# UVglasses.net
KiCad netlist of a schematic drawn in EAGLE
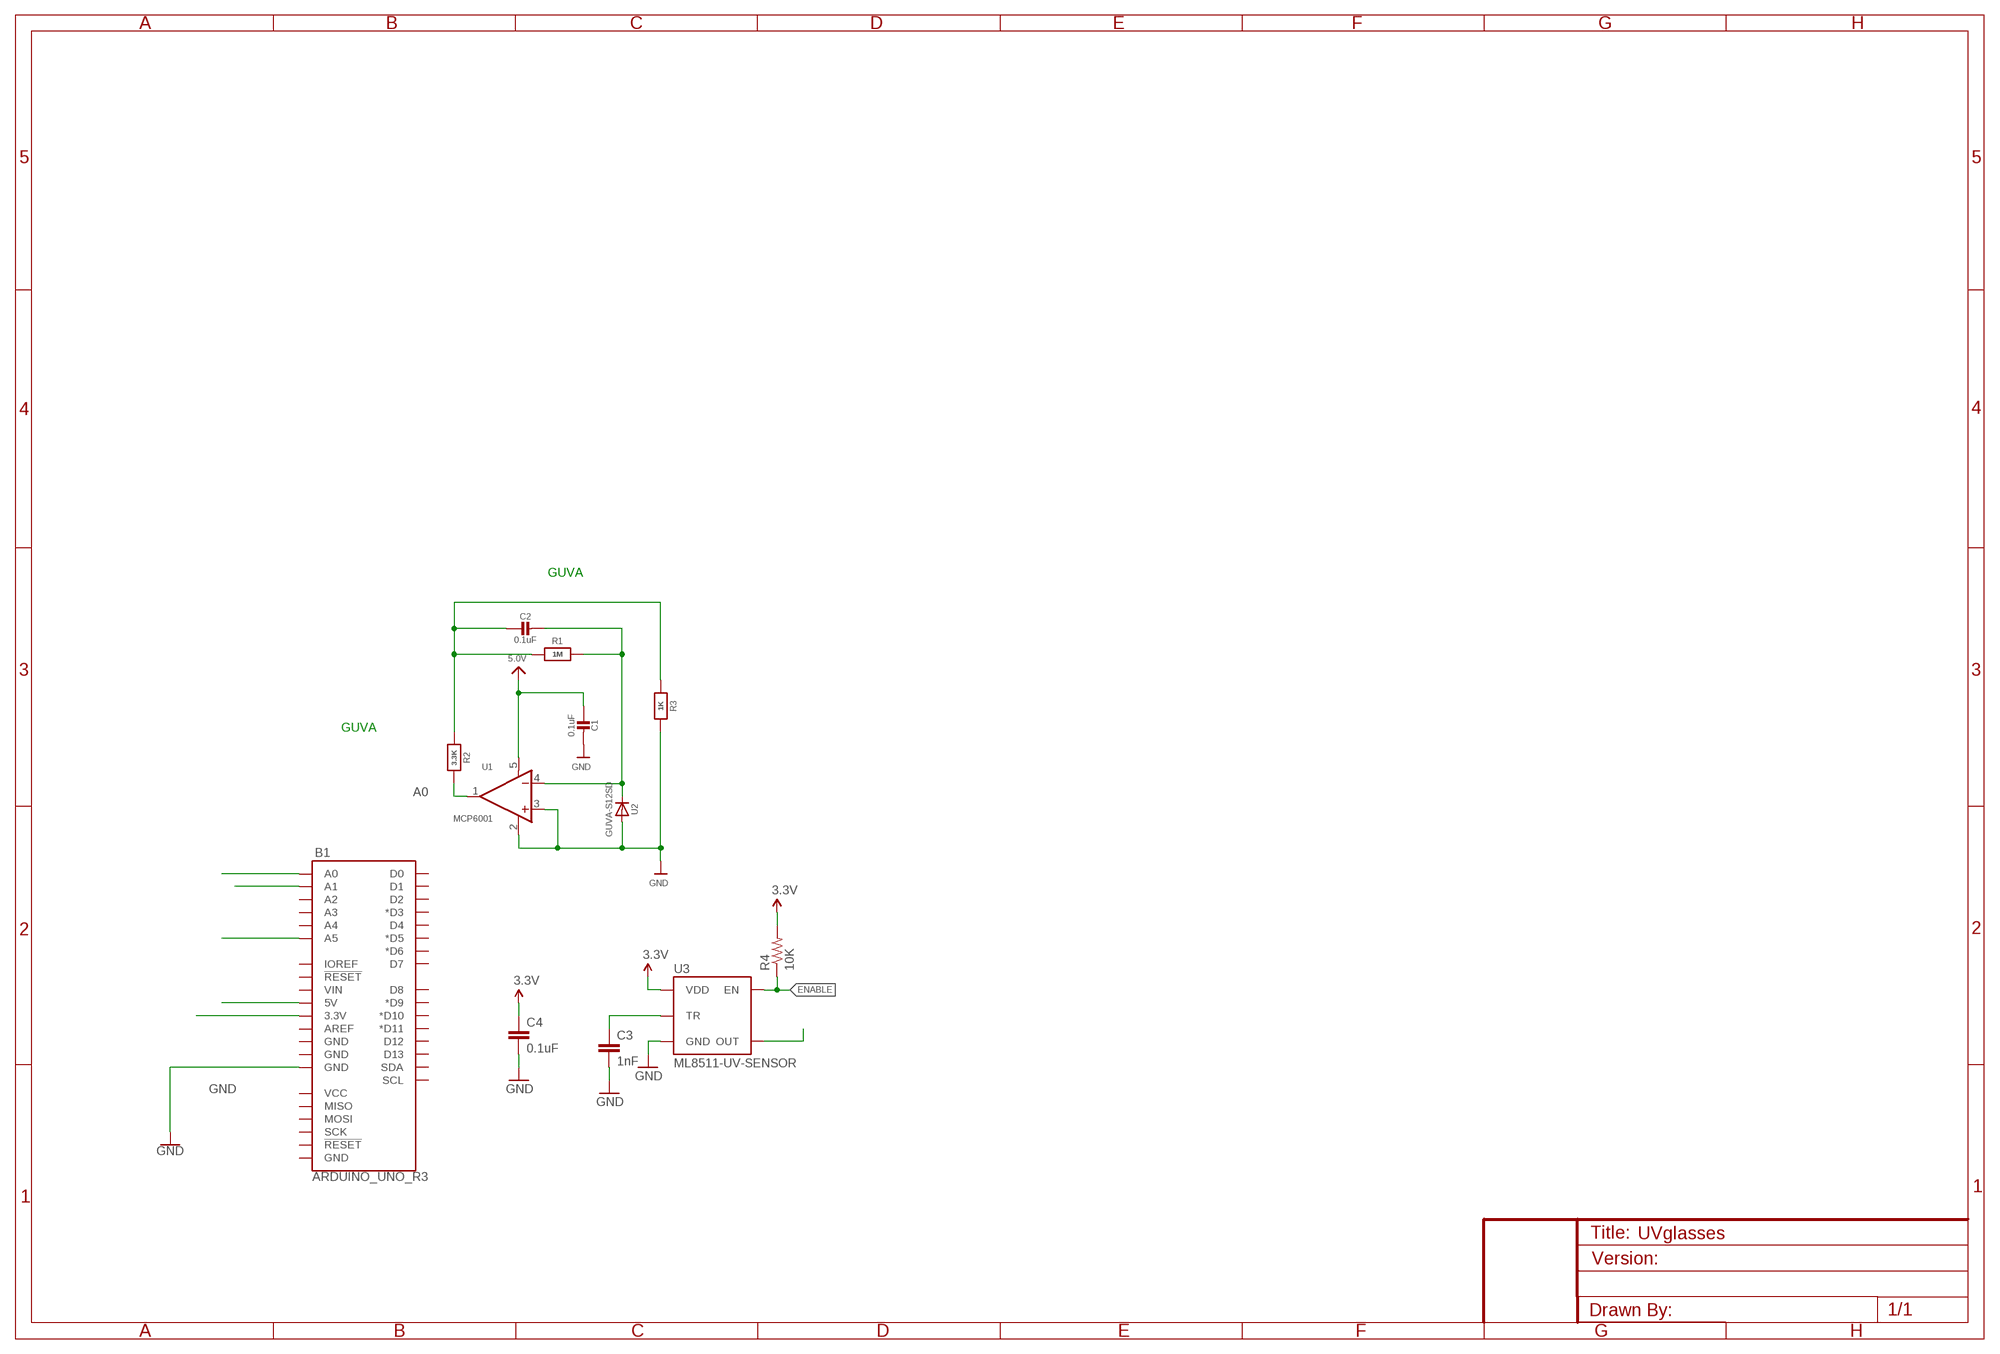
[diagram p0: schematic, sheet 1]

(export (version "E")
  (design (tool "Eeschema 10.0.6"))
  (components
    (comp (ref "B1")
      (value "ARDUINO_UNO_R3")
      (footprint "eagle-import:ARDUINO_R3")
      (libsource (lib "eagle-import") (part "ARDUINO_UNO_R3"))
    )
    (comp (ref "C1")
      (value "0.1uF")
      (footprint "eagle-import:0805-NO")
      (libsource (lib "eagle-import") (part "CAP_CERAMIC0805-NOOUTLINE"))
    )
    (comp (ref "C2")
      (value "0.1uF")
      (footprint "eagle-import:0805-NO")
      (libsource (lib "eagle-import") (part "CAP_CERAMIC0805-NOOUTLINE"))
    )
    (comp (ref "C3")
      (value "1nF")
      (footprint "eagle-import:0603-CAP")
      (libsource (lib "eagle-import") (part "1NF/1000PF-50V-10%(0603)"))
    )
    (comp (ref "C4")
      (value "0.1uF")
      (footprint "eagle-import:0603-CAP")
      (libsource (lib "eagle-import") (part "0.1UF-25V(+80/-20%)(0603)"))
    )
    (comp (ref "R1")
      (value "1M")
      (footprint "eagle-import:0805-NO")
      (libsource (lib "eagle-import") (part "RESISTOR0805_NOOUTLINE"))
    )
    (comp (ref "R2")
      (value "3.3K")
      (footprint "eagle-import:0805-NO")
      (libsource (lib "eagle-import") (part "RESISTOR0805_NOOUTLINE"))
    )
    (comp (ref "R3")
      (value "1K")
      (footprint "eagle-import:0805-NO")
      (libsource (lib "eagle-import") (part "RESISTOR0805_NOOUTLINE"))
    )
    (comp (ref "R4")
      (value "10K")
      (footprint "eagle-import:0603-RES")
      (libsource (lib "eagle-import") (part "10KOHM1/10W1%(0603)0603"))
    )
    (comp (ref "U1")
      (value "MCP6001")
      (footprint "eagle-import:SOT23-5")
      (libsource (lib "eagle-import") (part "OPAMP_SINGLESOT235"))
    )
    (comp (ref "U2")
      (value "GUVA-S12SD")
      (footprint "eagle-import:GUVA-S12SD")
      (libsource (lib "eagle-import") (part "UV_GUVA-S12SD"))
    )
    (comp (ref "U3")
      (value "ML8511-UV-SENSOR")
      (footprint "eagle-import:ML8511")
      (libsource (lib "eagle-import") (part "ML8511-UV-SENSORSMD"))
    )
  )
  (nets
    (net (code "1") (name "/A0") (class "Default")
      (node (ref "B1") (pin "A0") (pinfunction "A0_A0") (pintype "bidirectional"))
      (node (ref "R2") (pin "1") (pinfunction "1_1") (pintype "passive"))
      (node (ref "U1") (pin "1") (pinfunction "OUT_1") (pintype "output"))
    )
    (net (code "2") (name "/A1") (class "Default")
      (node (ref "B1") (pin "A1") (pinfunction "A1_A1") (pintype "bidirectional"))
      (node (ref "U3") (pin "8") (pinfunction "OUT_8") (pintype "output"))
    )
    (net (code "3") (name "3.3V") (class "Default")
      (node (ref "B1") (pin "3.3V") (pinfunction "3.3V_3.3V") (pintype "bidirectional"))
      (node (ref "B1") (pin "A5") (pinfunction "A5_A5") (pintype "bidirectional"))
      (node (ref "C4") (pin "1") (pinfunction "1_1") (pintype "passive"))
      (node (ref "R4") (pin "2") (pinfunction "2_2") (pintype "passive"))
      (node (ref "U3") (pin "7") (pinfunction "VDD_7") (pintype "power_in"))
    )
    (net (code "4") (name "5.0V") (class "Default")
      (node (ref "B1") (pin "5V") (pinfunction "5V_5V") (pintype "bidirectional"))
      (node (ref "C1") (pin "1") (pinfunction "1_1") (pintype "passive"))
      (node (ref "U1") (pin "5") (pinfunction "V+_5") (pintype "power_in"))
    )
    (net (code "5") (name "ENABLE") (class "Default")
      (node (ref "R4") (pin "1") (pinfunction "1_1") (pintype "passive"))
      (node (ref "U3") (pin "4") (pinfunction "EN_4") (pintype "input"))
    )
    (net (code "6") (name "GND") (class "Default")
      (node (ref "B1") (pin "GND@2") (pinfunction "GND_GND@2") (pintype "bidirectional"))
      (node (ref "C1") (pin "2") (pinfunction "2_2") (pintype "passive"))
      (node (ref "C3") (pin "2") (pinfunction "2_2") (pintype "passive"))
      (node (ref "C4") (pin "2") (pinfunction "2_2") (pintype "passive"))
      (node (ref "R3") (pin "1") (pinfunction "1_1") (pintype "passive"))
      (node (ref "U1") (pin "2") (pinfunction "V-_2") (pintype "power_in"))
      (node (ref "U1") (pin "3") (pinfunction "+IN_3") (pintype "input"))
      (node (ref "U2") (pin "A") (pinfunction "A_A") (pintype "passive"))
      (node (ref "U3") (pin "5") (pinfunction "GND_5") (pintype "power_in"))
    )
    (net (code "7") (name "Net-(C2-Pad1)") (class "Default")
      (node (ref "C2") (pin "1") (pinfunction "1_1") (pintype "passive"))
      (node (ref "R1") (pin "2") (pinfunction "2_2") (pintype "passive"))
      (node (ref "R2") (pin "2") (pinfunction "2_2") (pintype "passive"))
      (node (ref "R3") (pin "2") (pinfunction "2_2") (pintype "passive"))
    )
    (net (code "8") (name "Net-(U1--IN)") (class "Default")
      (node (ref "C2") (pin "2") (pinfunction "2_2") (pintype "passive"))
      (node (ref "R1") (pin "1") (pinfunction "1_1") (pintype "passive"))
      (node (ref "U1") (pin "4") (pinfunction "-IN_4") (pintype "input"))
      (node (ref "U2") (pin "K") (pinfunction "C_K") (pintype "passive"))
    )
    (net (code "9") (name "Net-(U3-TR)") (class "Default")
      (node (ref "C3") (pin "1") (pinfunction "1_1") (pintype "passive"))
      (node (ref "U3") (pin "10") (pinfunction "TR_10") (pintype "power_in"))
    )
    (net (code "10") (name "unconnected-(B1-*D3-PadD3)") (class "Default")
      (node (ref "B1") (pin "D3") (pinfunction "*D3_D3") (pintype "bidirectional"))
    )
    (net (code "11") (name "unconnected-(B1-*D5-PadD5)") (class "Default")
      (node (ref "B1") (pin "D5") (pinfunction "*D5_D5") (pintype "bidirectional"))
    )
    (net (code "12") (name "unconnected-(B1-*D6-PadD6)") (class "Default")
      (node (ref "B1") (pin "D6") (pinfunction "*D6_D6") (pintype "bidirectional"))
    )
    (net (code "13") (name "unconnected-(B1-*D9-PadD9)") (class "Default")
      (node (ref "B1") (pin "D9") (pinfunction "*D9_D9") (pintype "bidirectional"))
    )
    (net (code "14") (name "unconnected-(B1-*D10-PadD10)") (class "Default")
      (node (ref "B1") (pin "D10") (pinfunction "*D10_D10") (pintype "bidirectional"))
    )
    (net (code "15") (name "unconnected-(B1-*D11-PadD11)") (class "Default")
      (node (ref "B1") (pin "D11") (pinfunction "*D11_D11") (pintype "bidirectional"))
    )
    (net (code "16") (name "unconnected-(B1-GND-PadGND@1)") (class "Default")
      (node (ref "B1") (pin "GND@1") (pinfunction "GND_GND@1") (pintype "bidirectional"))
    )
    (net (code "17") (name "unconnected-(B1-GND-PadGND@3)") (class "Default")
      (node (ref "B1") (pin "GND@3") (pinfunction "GND_GND@3") (pintype "bidirectional"))
    )
    (net (code "18") (name "unconnected-(B1-GND-PadGND@4)") (class "Default")
      (node (ref "B1") (pin "GND@4") (pinfunction "GND_GND@4") (pintype "bidirectional"))
    )
    (net (code "19") (name "unconnected-(B1-PadA2)") (class "Default")
      (node (ref "B1") (pin "A2") (pinfunction "A2_A2") (pintype "bidirectional"))
    )
    (net (code "20") (name "unconnected-(B1-PadA3)") (class "Default")
      (node (ref "B1") (pin "A3") (pinfunction "A3_A3") (pintype "bidirectional"))
    )
    (net (code "21") (name "unconnected-(B1-PadA4)") (class "Default")
      (node (ref "B1") (pin "A4") (pinfunction "A4_A4") (pintype "bidirectional"))
    )
    (net (code "22") (name "unconnected-(B1-PadAREF)") (class "Default")
      (node (ref "B1") (pin "AREF") (pinfunction "AREF_AREF") (pintype "bidirectional"))
    )
    (net (code "23") (name "unconnected-(B1-PadD0)") (class "Default")
      (node (ref "B1") (pin "D0") (pinfunction "D0_D0") (pintype "bidirectional"))
    )
    (net (code "24") (name "unconnected-(B1-PadD1)") (class "Default")
      (node (ref "B1") (pin "D1") (pinfunction "D1_D1") (pintype "bidirectional"))
    )
    (net (code "25") (name "unconnected-(B1-PadD2)") (class "Default")
      (node (ref "B1") (pin "D2") (pinfunction "D2_D2") (pintype "bidirectional"))
    )
    (net (code "26") (name "unconnected-(B1-PadD4)") (class "Default")
      (node (ref "B1") (pin "D4") (pinfunction "D4_D4") (pintype "bidirectional"))
    )
    (net (code "27") (name "unconnected-(B1-PadD7)") (class "Default")
      (node (ref "B1") (pin "D7") (pinfunction "D7_D7") (pintype "bidirectional"))
    )
    (net (code "28") (name "unconnected-(B1-PadD8)") (class "Default")
      (node (ref "B1") (pin "D8") (pinfunction "D8_D8") (pintype "bidirectional"))
    )
    (net (code "29") (name "unconnected-(B1-PadD12)") (class "Default")
      (node (ref "B1") (pin "D12") (pinfunction "D12_D12") (pintype "bidirectional"))
    )
    (net (code "30") (name "unconnected-(B1-PadD13)") (class "Default")
      (node (ref "B1") (pin "D13") (pinfunction "D13_D13") (pintype "bidirectional"))
    )
    (net (code "31") (name "unconnected-(B1-PadIOREF)") (class "Default")
      (node (ref "B1") (pin "IOREF") (pinfunction "IOREF_IOREF") (pintype "bidirectional"))
    )
    (net (code "32") (name "unconnected-(B1-PadMISO)") (class "Default")
      (node (ref "B1") (pin "MISO") (pinfunction "MISO_MISO") (pintype "bidirectional"))
    )
    (net (code "33") (name "unconnected-(B1-PadMOSI)") (class "Default")
      (node (ref "B1") (pin "MOSI") (pinfunction "MOSI_MOSI") (pintype "bidirectional"))
    )
    (net (code "34") (name "unconnected-(B1-PadSCK)") (class "Default")
      (node (ref "B1") (pin "SCK") (pinfunction "SCK_SCK") (pintype "bidirectional"))
    )
    (net (code "35") (name "unconnected-(B1-PadSCL)") (class "Default")
      (node (ref "B1") (pin "SCL") (pinfunction "SCL_SCL") (pintype "bidirectional"))
    )
    (net (code "36") (name "unconnected-(B1-PadSDA)") (class "Default")
      (node (ref "B1") (pin "SDA") (pinfunction "SDA_SDA") (pintype "bidirectional"))
    )
    (net (code "37") (name "unconnected-(B1-PadVCC)") (class "Default")
      (node (ref "B1") (pin "VCC") (pinfunction "VCC_VCC") (pintype "bidirectional"))
    )
    (net (code "38") (name "unconnected-(B1-PadVIN)") (class "Default")
      (node (ref "B1") (pin "VIN") (pinfunction "VIN_VIN") (pintype "bidirectional"))
    )
    (net (code "39") (name "unconnected-(B1-~{RESET}-PadRESET@1)") (class "Default")
      (node (ref "B1") (pin "RESET@1") (pinfunction "~{RESET}_RESET@1") (pintype "bidirectional"))
    )
    (net (code "40") (name "unconnected-(B1-~{RESET}-PadRESET@2)") (class "Default")
      (node (ref "B1") (pin "RESET@2") (pinfunction "~{RESET}_RESET@2") (pintype "bidirectional"))
    )
  )
)
